# redashboard_rp2040.net
KiCad netlist of a schematic drawn in EAGLE
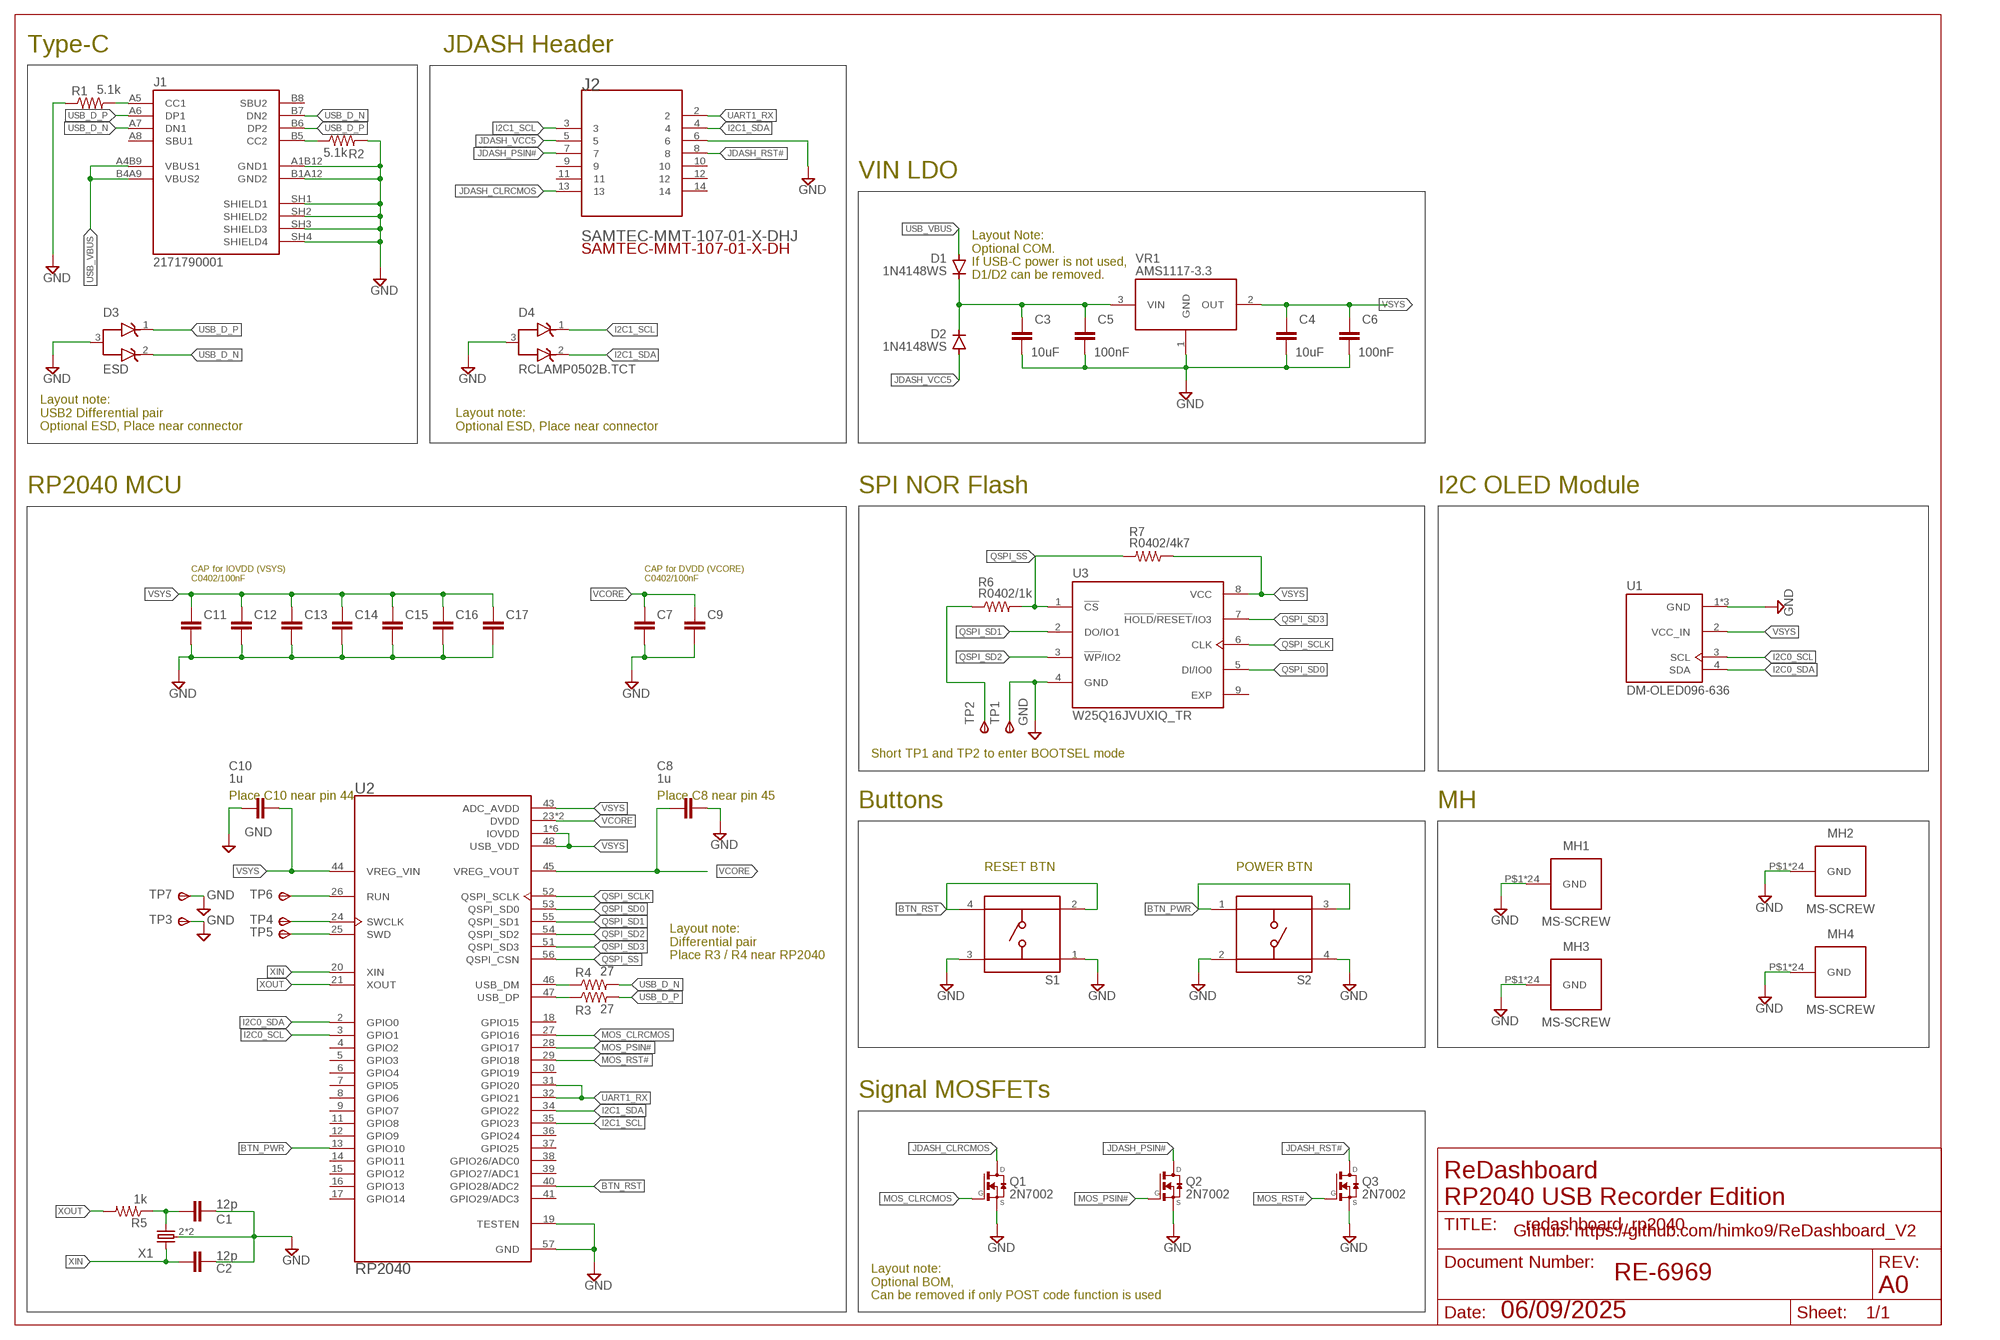
[diagram p0: schematic, sheet 1]

(export (version "E")
  (design (tool "Eeschema 10.0.6"))
  (components
    (comp (ref "C1")
      (value "12p")
      (footprint "eagle-import:CAP_0402")
      (fields
        (field (name "DIGIKEY_PART_NUMBER") "311-1014-2-ND")
        (field (name "MANUFACTURER") "Yageo")
        (field (name "MPN") "CC0402JRNPO9BN100")
        (field (name "CREATED_BY") "PCBLayout.com")
      )
      (libsource (lib "eagle-import") (part "CC0402JRNPO9BN100"))
    )
    (comp (ref "C2")
      (value "12p")
      (footprint "eagle-import:CAP_0402")
      (fields
        (field (name "DIGIKEY_PART_NUMBER") "311-1014-2-ND")
        (field (name "MANUFACTURER") "Yageo")
        (field (name "MPN") "CC0402JRNPO9BN100")
        (field (name "CREATED_BY") "PCBLayout.com")
      )
      (libsource (lib "eagle-import") (part "CC0402JRNPO9BN100"))
    )
    (comp (ref "C3")
      (value "10uF")
      (footprint "eagle-import:CAP_0603")
      (fields
        (field (name "DIGIKEY_PART_NUMBER") "311-1063-2-ND")
        (field (name "MANUFACTURER") "Yageo")
        (field (name "MPN") "CC0603JRNPO9BN270")
        (field (name "CREATED_BY") "PCBLayout.com")
      )
      (libsource (lib "eagle-import") (part "CC0603JRNPO9BN270"))
    )
    (comp (ref "C4")
      (value "10uF")
      (footprint "eagle-import:CAP_0603")
      (fields
        (field (name "DIGIKEY_PART_NUMBER") "311-1063-2-ND")
        (field (name "MANUFACTURER") "Yageo")
        (field (name "MPN") "CC0603JRNPO9BN270")
        (field (name "CREATED_BY") "PCBLayout.com")
      )
      (libsource (lib "eagle-import") (part "CC0603JRNPO9BN270"))
    )
    (comp (ref "C5")
      (value "100nF")
      (footprint "eagle-import:CAP_0402")
      (fields
        (field (name "DIGIKEY_PART_NUMBER") "311-2076-2-ND")
        (field (name "MANUFACTURER") "Yageo")
        (field (name "MPN") "CC0402CRNPO9BN1R0")
        (field (name "CREATED_BY") "PCBLayout.com")
      )
      (libsource (lib "eagle-import") (part "CC0402CRNPO9BN1R0"))
    )
    (comp (ref "C6")
      (value "100nF")
      (footprint "eagle-import:CAP_0402")
      (fields
        (field (name "DIGIKEY_PART_NUMBER") "311-2076-2-ND")
        (field (name "MANUFACTURER") "Yageo")
        (field (name "MPN") "CC0402CRNPO9BN1R0")
        (field (name "CREATED_BY") "PCBLayout.com")
      )
      (libsource (lib "eagle-import") (part "CC0402CRNPO9BN1R0"))
    )
    (comp (ref "C7")
      (value "100nF")
      (footprint "eagle-import:CAP_0402")
      (fields
        (field (name "DIGIKEY_PART_NUMBER") "311-2076-2-ND")
        (field (name "MANUFACTURER") "Yageo")
        (field (name "MPN") "CC0402CRNPO9BN1R0")
        (field (name "CREATED_BY") "PCBLayout.com")
      )
      (libsource (lib "eagle-import") (part "CC0402CRNPO9BN1R0"))
    )
    (comp (ref "C8")
      (value "1u")
      (footprint "eagle-import:CAP_0402")
      (fields
        (field (name "DIGIKEY_PART_NUMBER") "311-2076-2-ND")
        (field (name "MANUFACTURER") "Yageo")
        (field (name "MPN") "CC0402CRNPO9BN1R0")
        (field (name "CREATED_BY") "PCBLayout.com")
      )
      (libsource (lib "eagle-import") (part "CC0402CRNPO9BN1R0"))
    )
    (comp (ref "C9")
      (value "CC0402CRNPO9BN1R0")
      (footprint "eagle-import:CAP_0402")
      (fields
        (field (name "DIGIKEY_PART_NUMBER") "311-2076-2-ND")
        (field (name "MANUFACTURER") "Yageo")
        (field (name "CREATED_BY") "PCBLayout.com")
      )
      (libsource (lib "eagle-import") (part "CC0402CRNPO9BN1R0"))
    )
    (comp (ref "C10")
      (value "1u")
      (footprint "eagle-import:CAP_0402")
      (fields
        (field (name "DIGIKEY_PART_NUMBER") "311-2076-2-ND")
        (field (name "MANUFACTURER") "Yageo")
        (field (name "MPN") "CC0402CRNPO9BN1R0")
        (field (name "CREATED_BY") "PCBLayout.com")
      )
      (libsource (lib "eagle-import") (part "CC0402CRNPO9BN1R0"))
    )
    (comp (ref "C11")
      (value "100nF")
      (footprint "eagle-import:CAP_0402")
      (fields
        (field (name "DIGIKEY_PART_NUMBER") "311-2076-2-ND")
        (field (name "MANUFACTURER") "Yageo")
        (field (name "MPN") "CC0402CRNPO9BN1R0")
        (field (name "CREATED_BY") "PCBLayout.com")
      )
      (libsource (lib "eagle-import") (part "CC0402CRNPO9BN1R0"))
    )
    (comp (ref "C12")
      (value "100nF")
      (footprint "eagle-import:CAP_0402")
      (fields
        (field (name "DIGIKEY_PART_NUMBER") "311-2076-2-ND")
        (field (name "MANUFACTURER") "Yageo")
        (field (name "MPN") "CC0402CRNPO9BN1R0")
        (field (name "CREATED_BY") "PCBLayout.com")
      )
      (libsource (lib "eagle-import") (part "CC0402CRNPO9BN1R0"))
    )
    (comp (ref "C13")
      (value "100nF")
      (footprint "eagle-import:CAP_0402")
      (fields
        (field (name "DIGIKEY_PART_NUMBER") "311-2076-2-ND")
        (field (name "MANUFACTURER") "Yageo")
        (field (name "MPN") "CC0402CRNPO9BN1R0")
        (field (name "CREATED_BY") "PCBLayout.com")
      )
      (libsource (lib "eagle-import") (part "CC0402CRNPO9BN1R0"))
    )
    (comp (ref "C14")
      (value "100nF")
      (footprint "eagle-import:CAP_0402")
      (fields
        (field (name "DIGIKEY_PART_NUMBER") "311-2076-2-ND")
        (field (name "MANUFACTURER") "Yageo")
        (field (name "MPN") "CC0402CRNPO9BN1R0")
        (field (name "CREATED_BY") "PCBLayout.com")
      )
      (libsource (lib "eagle-import") (part "CC0402CRNPO9BN1R0"))
    )
    (comp (ref "C15")
      (value "100nF")
      (footprint "eagle-import:CAP_0402")
      (fields
        (field (name "DIGIKEY_PART_NUMBER") "311-2076-2-ND")
        (field (name "MANUFACTURER") "Yageo")
        (field (name "MPN") "CC0402CRNPO9BN1R0")
        (field (name "CREATED_BY") "PCBLayout.com")
      )
      (libsource (lib "eagle-import") (part "CC0402CRNPO9BN1R0"))
    )
    (comp (ref "C16")
      (value "100nF")
      (footprint "eagle-import:CAP_0402")
      (fields
        (field (name "DIGIKEY_PART_NUMBER") "311-2076-2-ND")
        (field (name "MANUFACTURER") "Yageo")
        (field (name "MPN") "CC0402CRNPO9BN1R0")
        (field (name "CREATED_BY") "PCBLayout.com")
      )
      (libsource (lib "eagle-import") (part "CC0402CRNPO9BN1R0"))
    )
    (comp (ref "C17")
      (value "100nF")
      (footprint "eagle-import:CAP_0402")
      (fields
        (field (name "DIGIKEY_PART_NUMBER") "311-2076-2-ND")
        (field (name "MANUFACTURER") "Yageo")
        (field (name "MPN") "CC0402CRNPO9BN1R0")
        (field (name "CREATED_BY") "PCBLayout.com")
      )
      (libsource (lib "eagle-import") (part "CC0402CRNPO9BN1R0"))
    )
    (comp (ref "D1")
      (value "1N4148WS")
      (footprint "eagle-import:SOD-323")
      (fields
        (field (name "DIGIKEY_PART_NUMBER") "1N4148WSFSTR-ND")
        (field (name "MANUFACTURER") "Diodes Incorporated")
        (field (name "CREATED_BY") "PCBLayout.com")
      )
      (libsource (lib "eagle-import") (part "1N4148WS"))
    )
    (comp (ref "D2")
      (value "1N4148WS")
      (footprint "eagle-import:SOD-323")
      (fields
        (field (name "DIGIKEY_PART_NUMBER") "1N4148WSFSTR-ND")
        (field (name "MANUFACTURER") "Diodes Incorporated")
        (field (name "CREATED_BY") "PCBLayout.com")
      )
      (libsource (lib "eagle-import") (part "1N4148WS"))
    )
    (comp (ref "D3")
      (value "ESD")
      (footprint "eagle-import:TVS_RCLAMP0502B.TCT")
      (fields (field (name "MF") "Semtech Corporation") (field (name "MP") "RCLAMP0502B.TCT"))
      (libsource (lib "eagle-import") (part "RCLAMP0502B.TCT"))
    )
    (comp (ref "D4")
      (value "RCLAMP0502B.TCT")
      (footprint "eagle-import:TVS_RCLAMP0502B.TCT")
      (fields (field (name "MF") "Semtech Corporation"))
      (libsource (lib "eagle-import") (part "RCLAMP0502B.TCT"))
    )
    (comp (ref "J1")
      (value "2171790001")
      (footprint "eagle-import:MOLEX_2171790001")
      (fields (field (name "MF") "Molex"))
      (libsource (lib "eagle-import") (part "2171790001"))
    )
    (comp (ref "J2")
      (value "SAMTEC-MMT-107-01-X-DHJ")
      (footprint "eagle-import:SAMTEC-MMT-107-01-X-DH")
      (fields (field (name "MF") "Samtec") (field (name "MP") "MMT-107-01-S-DH-P-TR"))
      (libsource (lib "eagle-import") (part "SAMTEC-MMT-107-01-X-DHJ"))
    )
    (comp (ref "MH1")
      (value "MS-SCREW")
      (footprint "eagle-import:MS-SCREW")
      (libsource (lib "eagle-import") (part "MS-SCREW"))
    )
    (comp (ref "MH2")
      (value "MS-SCREW")
      (footprint "eagle-import:MS-SCREW")
      (libsource (lib "eagle-import") (part "MS-SCREW"))
    )
    (comp (ref "MH3")
      (value "MS-SCREW")
      (footprint "eagle-import:MS-SCREW")
      (libsource (lib "eagle-import") (part "MS-SCREW"))
    )
    (comp (ref "MH4")
      (value "MS-SCREW")
      (footprint "eagle-import:MS-SCREW")
      (libsource (lib "eagle-import") (part "MS-SCREW"))
    )
    (comp (ref "Q1")
      (value "2N7002")
      (footprint "eagle-import:TRANSISTOR-FET_SOT23")
      (libsource (lib "eagle-import") (part "TRANSISTOR-FET_DMN2004K"))
    )
    (comp (ref "Q2")
      (value "2N7002")
      (footprint "eagle-import:TRANSISTOR-FET_SOT23")
      (libsource (lib "eagle-import") (part "TRANSISTOR-FET_DMN2004K"))
    )
    (comp (ref "Q3")
      (value "2N7002")
      (footprint "eagle-import:TRANSISTOR-FET_SOT23")
      (libsource (lib "eagle-import") (part "TRANSISTOR-FET_DMN2004K"))
    )
    (comp (ref "R1")
      (value "5.1k")
      (footprint "eagle-import:RES_0402")
      (fields
        (field (name "DIGIKEY_PART_NUMBER") "311-0.0JRTR-ND")
        (field (name "MANUFACTURER") "Yageo")
        (field (name "MPN") "RC0402JR-070RL")
        (field (name "CREATED_BY") "PCBLayout.com")
      )
      (libsource (lib "eagle-import") (part "RC0402JR-070RL"))
    )
    (comp (ref "R2")
      (value "5.1k")
      (footprint "eagle-import:RES_0402")
      (fields
        (field (name "DIGIKEY_PART_NUMBER") "311-0.0JRTR-ND")
        (field (name "MANUFACTURER") "Yageo")
        (field (name "MPN") "RC0402JR-070RL")
        (field (name "CREATED_BY") "PCBLayout.com")
      )
      (libsource (lib "eagle-import") (part "RC0402JR-070RL"))
    )
    (comp (ref "R3")
      (value "27")
      (footprint "eagle-import:RES_0402")
      (fields
        (field (name "DIGIKEY_PART_NUMBER") "311-0.0JRTR-ND")
        (field (name "MANUFACTURER") "Yageo")
        (field (name "MPN") "RC0402JR-070RL")
        (field (name "CREATED_BY") "PCBLayout.com")
      )
      (libsource (lib "eagle-import") (part "RC0402JR-070RL"))
    )
    (comp (ref "R4")
      (value "27")
      (footprint "eagle-import:RES_0402")
      (fields
        (field (name "DIGIKEY_PART_NUMBER") "311-0.0JRTR-ND")
        (field (name "MANUFACTURER") "Yageo")
        (field (name "MPN") "RC0402JR-070RL")
        (field (name "CREATED_BY") "PCBLayout.com")
      )
      (libsource (lib "eagle-import") (part "RC0402JR-070RL"))
    )
    (comp (ref "R5")
      (value "1k")
      (footprint "eagle-import:RES_0402")
      (fields
        (field (name "DIGIKEY_PART_NUMBER") "311-0.0JRTR-ND")
        (field (name "MANUFACTURER") "Yageo")
        (field (name "MPN") "RC0402JR-070RL")
        (field (name "CREATED_BY") "PCBLayout.com")
      )
      (libsource (lib "eagle-import") (part "RC0402JR-070RL"))
    )
    (comp (ref "R6")
      (value "R0402/1k")
      (footprint "eagle-import:RES_0402")
      (fields
        (field (name "DIGIKEY_PART_NUMBER") "311-0.0JRTR-ND")
        (field (name "MANUFACTURER") "Yageo")
        (field (name "MPN") "RC0402JR-070RL")
        (field (name "CREATED_BY") "PCBLayout.com")
      )
      (libsource (lib "eagle-import") (part "RC0402JR-070RL"))
    )
    (comp (ref "R7")
      (value "R0402/4k7")
      (footprint "eagle-import:RES_0402")
      (fields
        (field (name "DIGIKEY_PART_NUMBER") "311-0.0JRTR-ND")
        (field (name "MANUFACTURER") "Yageo")
        (field (name "MPN") "RC0402JR-070RL")
        (field (name "CREATED_BY") "PCBLayout.com")
      )
      (libsource (lib "eagle-import") (part "RC0402JR-070RL"))
    )
    (comp (ref "S1")
      (value "TS04-66-50-BK-260-SMT")
      (footprint "eagle-import:SW_TS04-66-50-BK-260-SMT")
      (fields (field (name "MF") "Same Sky"))
      (libsource (lib "eagle-import") (part "TS04-66-50-BK-260-SMT"))
    )
    (comp (ref "S2")
      (value "TS04-66-50-BK-260-SMT")
      (footprint "eagle-import:SW_TS04-66-50-BK-260-SMT")
      (fields (field (name "MF") "Same Sky"))
      (libsource (lib "eagle-import") (part "TS04-66-50-BK-260-SMT"))
    )
    (comp (ref "TP1")
      (value "TPSTP10SQ")
      (footprint "eagle-import:TP10SQ")
      (libsource (lib "eagle-import") (part "TPSTP10SQ"))
    )
    (comp (ref "TP2")
      (value "TPSTP10R")
      (footprint "eagle-import:TP10R")
      (libsource (lib "eagle-import") (part "TPSTP10R"))
    )
    (comp (ref "TP3")
      (value "TPSTP10SQ")
      (footprint "eagle-import:TP10SQ")
      (libsource (lib "eagle-import") (part "TPSTP10SQ"))
    )
    (comp (ref "TP4")
      (value "TPSTP10R")
      (footprint "eagle-import:TP10R")
      (libsource (lib "eagle-import") (part "TPSTP10R"))
    )
    (comp (ref "TP5")
      (value "TPSTP10R")
      (footprint "eagle-import:TP10R")
      (libsource (lib "eagle-import") (part "TPSTP10R"))
    )
    (comp (ref "TP6")
      (value "TPSTP10R")
      (footprint "eagle-import:TP10R")
      (libsource (lib "eagle-import") (part "TPSTP10R"))
    )
    (comp (ref "TP7")
      (value "TPSTP10SQ")
      (footprint "eagle-import:TP10SQ")
      (libsource (lib "eagle-import") (part "TPSTP10SQ"))
    )
    (comp (ref "U1")
      (value "DM-OLED096-636")
      (footprint "eagle-import:MODULE_DM-OLED096-636")
      (fields (field (name "MF") "Display Module"))
      (libsource (lib "eagle-import") (part "DM-OLED096-636"))
    )
    (comp (ref "U2")
      (value "RP2040")
      (footprint "eagle-import:QFN40P700X700X90-57N")
      (fields (field (name "MF") "Raspberry Pi"))
      (libsource (lib "eagle-import") (part "RP2040"))
    )
    (comp (ref "U3")
      (value "W25Q16JVUXIQ_TR")
      (footprint "eagle-import:IC_W25Q16JVUXIQ_TR")
      (fields (field (name "MF") "Winbond") (field (name "MP") "W25Q16JVUXIQ TR"))
      (libsource (lib "eagle-import") (part "W25Q16JVUXIQ_TR"))
    )
    (comp (ref "VR1")
      (value "AMS1117-3.3")
      (footprint "eagle-import:VREG_AZ1117CR2-5.0TRG1")
      (fields (field (name "MF") "Diodes Zetex") (field (name "MP") "AZ1117CR2-5.0TRG1"))
      (libsource (lib "eagle-import") (part "AZ1117CR2-5.0TRG1"))
    )
    (comp (ref "X1")
      (value "KX-6")
      (footprint "eagle-import:2.5X2.0_KX-6")
      (libsource (lib "eagle-import") (part "KX-6"))
    )
  )
  (nets
    (net (code "1") (name "BTN_PWR") (class "Default")
      (node (ref "S2") (pin "1") (pinfunction "1_1") (pintype "passive"))
      (node (ref "S2") (pin "3") (pinfunction "3_3") (pintype "passive"))
      (node (ref "U2") (pin "13") (pinfunction "GPIO10_13") (pintype "bidirectional"))
    )
    (net (code "2") (name "BTN_RST") (class "Default")
      (node (ref "S1") (pin "2") (pinfunction "2_2") (pintype "passive"))
      (node (ref "S1") (pin "4") (pinfunction "4_4") (pintype "passive"))
      (node (ref "U2") (pin "40") (pinfunction "GPIO28/ADC2_40") (pintype "bidirectional"))
    )
    (net (code "3") (name "GND") (class "Default")
      (node (ref "C1") (pin "2") (pinfunction "2_2") (pintype "passive"))
      (node (ref "C10") (pin "1") (pinfunction "1_1") (pintype "passive"))
      (node (ref "C11") (pin "2") (pinfunction "2_2") (pintype "passive"))
      (node (ref "C12") (pin "2") (pinfunction "2_2") (pintype "passive"))
      (node (ref "C13") (pin "2") (pinfunction "2_2") (pintype "passive"))
      (node (ref "C14") (pin "2") (pinfunction "2_2") (pintype "passive"))
      (node (ref "C15") (pin "2") (pinfunction "2_2") (pintype "passive"))
      (node (ref "C16") (pin "2") (pinfunction "2_2") (pintype "passive"))
      (node (ref "C17") (pin "2") (pinfunction "2_2") (pintype "passive"))
      (node (ref "C2") (pin "2") (pinfunction "2_2") (pintype "passive"))
      (node (ref "C3") (pin "2") (pinfunction "2_2") (pintype "passive"))
      (node (ref "C4") (pin "2") (pinfunction "2_2") (pintype "passive"))
      (node (ref "C5") (pin "2") (pinfunction "2_2") (pintype "passive"))
      (node (ref "C6") (pin "2") (pinfunction "2_2") (pintype "passive"))
      (node (ref "C7") (pin "2") (pinfunction "2_2") (pintype "passive"))
      (node (ref "C8") (pin "2") (pinfunction "2_2") (pintype "passive"))
      (node (ref "C9") (pin "2") (pinfunction "2_2") (pintype "passive"))
      (node (ref "D3") (pin "3") (pinfunction "A_3") (pintype "passive"))
      (node (ref "D4") (pin "3") (pinfunction "A_3") (pintype "passive"))
      (node (ref "J1") (pin "A1B12") (pinfunction "GND1_A1B12") (pintype "power_in"))
      (node (ref "J1") (pin "B1A12") (pinfunction "GND2_B1A12") (pintype "power_in"))
      (node (ref "J1") (pin "SH1") (pinfunction "SHIELD1_SH1") (pintype "passive"))
      (node (ref "J1") (pin "SH2") (pinfunction "SHIELD2_SH2") (pintype "passive"))
      (node (ref "J1") (pin "SH3") (pinfunction "SHIELD3_SH3") (pintype "passive"))
      (node (ref "J1") (pin "SH4") (pinfunction "SHIELD4_SH4") (pintype "passive"))
      (node (ref "J2") (pin "6") (pinfunction "6_6") (pintype "passive"))
      (node (ref "MH1") (pin "P$1") (pinfunction "GND_P$1") (pintype "bidirectional"))
      (node (ref "MH1") (pin "P$10") (pinfunction "GND_P$10") (pintype "bidirectional"))
      (node (ref "MH1") (pin "P$11") (pinfunction "GND_P$11") (pintype "bidirectional"))
      (node (ref "MH1") (pin "P$12") (pinfunction "GND_P$12") (pintype "bidirectional"))
      (node (ref "MH1") (pin "P$13") (pinfunction "GND_P$13") (pintype "bidirectional"))
      (node (ref "MH1") (pin "P$14") (pinfunction "GND_P$14") (pintype "bidirectional"))
      (node (ref "MH1") (pin "P$15") (pinfunction "GND_P$15") (pintype "bidirectional"))
      (node (ref "MH1") (pin "P$16") (pinfunction "GND_P$16") (pintype "bidirectional"))
      (node (ref "MH1") (pin "P$17") (pinfunction "GND_P$17") (pintype "bidirectional"))
      (node (ref "MH1") (pin "P$18") (pinfunction "GND_P$18") (pintype "bidirectional"))
      (node (ref "MH1") (pin "P$19") (pinfunction "GND_P$19") (pintype "bidirectional"))
      (node (ref "MH1") (pin "P$2") (pinfunction "GND_P$2") (pintype "bidirectional"))
      (node (ref "MH1") (pin "P$20") (pinfunction "GND_P$20") (pintype "bidirectional"))
      (node (ref "MH1") (pin "P$21") (pinfunction "GND_P$21") (pintype "bidirectional"))
      (node (ref "MH1") (pin "P$22") (pinfunction "GND_P$22") (pintype "bidirectional"))
      (node (ref "MH1") (pin "P$23") (pinfunction "GND_P$23") (pintype "bidirectional"))
      (node (ref "MH1") (pin "P$24") (pinfunction "GND_P$24") (pintype "bidirectional"))
      (node (ref "MH1") (pin "P$3") (pinfunction "GND_P$3") (pintype "bidirectional"))
      (node (ref "MH1") (pin "P$4") (pinfunction "GND_P$4") (pintype "bidirectional"))
      (node (ref "MH1") (pin "P$5") (pinfunction "GND_P$5") (pintype "bidirectional"))
      (node (ref "MH1") (pin "P$6") (pinfunction "GND_P$6") (pintype "bidirectional"))
      (node (ref "MH1") (pin "P$7") (pinfunction "GND_P$7") (pintype "bidirectional"))
      (node (ref "MH1") (pin "P$8") (pinfunction "GND_P$8") (pintype "bidirectional"))
      (node (ref "MH1") (pin "P$9") (pinfunction "GND_P$9") (pintype "bidirectional"))
      (node (ref "MH2") (pin "P$1") (pinfunction "GND_P$1") (pintype "bidirectional"))
      (node (ref "MH2") (pin "P$10") (pinfunction "GND_P$10") (pintype "bidirectional"))
      (node (ref "MH2") (pin "P$11") (pinfunction "GND_P$11") (pintype "bidirectional"))
      (node (ref "MH2") (pin "P$12") (pinfunction "GND_P$12") (pintype "bidirectional"))
      (node (ref "MH2") (pin "P$13") (pinfunction "GND_P$13") (pintype "bidirectional"))
      (node (ref "MH2") (pin "P$14") (pinfunction "GND_P$14") (pintype "bidirectional"))
      (node (ref "MH2") (pin "P$15") (pinfunction "GND_P$15") (pintype "bidirectional"))
      (node (ref "MH2") (pin "P$16") (pinfunction "GND_P$16") (pintype "bidirectional"))
      (node (ref "MH2") (pin "P$17") (pinfunction "GND_P$17") (pintype "bidirectional"))
      (node (ref "MH2") (pin "P$18") (pinfunction "GND_P$18") (pintype "bidirectional"))
      (node (ref "MH2") (pin "P$19") (pinfunction "GND_P$19") (pintype "bidirectional"))
      (node (ref "MH2") (pin "P$2") (pinfunction "GND_P$2") (pintype "bidirectional"))
      (node (ref "MH2") (pin "P$20") (pinfunction "GND_P$20") (pintype "bidirectional"))
      (node (ref "MH2") (pin "P$21") (pinfunction "GND_P$21") (pintype "bidirectional"))
      (node (ref "MH2") (pin "P$22") (pinfunction "GND_P$22") (pintype "bidirectional"))
      (node (ref "MH2") (pin "P$23") (pinfunction "GND_P$23") (pintype "bidirectional"))
      (node (ref "MH2") (pin "P$24") (pinfunction "GND_P$24") (pintype "bidirectional"))
      (node (ref "MH2") (pin "P$3") (pinfunction "GND_P$3") (pintype "bidirectional"))
      (node (ref "MH2") (pin "P$4") (pinfunction "GND_P$4") (pintype "bidirectional"))
      (node (ref "MH2") (pin "P$5") (pinfunction "GND_P$5") (pintype "bidirectional"))
      (node (ref "MH2") (pin "P$6") (pinfunction "GND_P$6") (pintype "bidirectional"))
      (node (ref "MH2") (pin "P$7") (pinfunction "GND_P$7") (pintype "bidirectional"))
      (node (ref "MH2") (pin "P$8") (pinfunction "GND_P$8") (pintype "bidirectional"))
      (node (ref "MH2") (pin "P$9") (pinfunction "GND_P$9") (pintype "bidirectional"))
      (node (ref "MH3") (pin "P$1") (pinfunction "GND_P$1") (pintype "bidirectional"))
      (node (ref "MH3") (pin "P$10") (pinfunction "GND_P$10") (pintype "bidirectional"))
      (node (ref "MH3") (pin "P$11") (pinfunction "GND_P$11") (pintype "bidirectional"))
      (node (ref "MH3") (pin "P$12") (pinfunction "GND_P$12") (pintype "bidirectional"))
      (node (ref "MH3") (pin "P$13") (pinfunction "GND_P$13") (pintype "bidirectional"))
      (node (ref "MH3") (pin "P$14") (pinfunction "GND_P$14") (pintype "bidirectional"))
      (node (ref "MH3") (pin "P$15") (pinfunction "GND_P$15") (pintype "bidirectional"))
      (node (ref "MH3") (pin "P$16") (pinfunction "GND_P$16") (pintype "bidirectional"))
      (node (ref "MH3") (pin "P$17") (pinfunction "GND_P$17") (pintype "bidirectional"))
      (node (ref "MH3") (pin "P$18") (pinfunction "GND_P$18") (pintype "bidirectional"))
      (node (ref "MH3") (pin "P$19") (pinfunction "GND_P$19") (pintype "bidirectional"))
      (node (ref "MH3") (pin "P$2") (pinfunction "GND_P$2") (pintype "bidirectional"))
      (node (ref "MH3") (pin "P$20") (pinfunction "GND_P$20") (pintype "bidirectional"))
      (node (ref "MH3") (pin "P$21") (pinfunction "GND_P$21") (pintype "bidirectional"))
      (node (ref "MH3") (pin "P$22") (pinfunction "GND_P$22") (pintype "bidirectional"))
      (node (ref "MH3") (pin "P$23") (pinfunction "GND_P$23") (pintype "bidirectional"))
      (node (ref "MH3") (pin "P$24") (pinfunction "GND_P$24") (pintype "bidirectional"))
      (node (ref "MH3") (pin "P$3") (pinfunction "GND_P$3") (pintype "bidirectional"))
      (node (ref "MH3") (pin "P$4") (pinfunction "GND_P$4") (pintype "bidirectional"))
      (node (ref "MH3") (pin "P$5") (pinfunction "GND_P$5") (pintype "bidirectional"))
      (node (ref "MH3") (pin "P$6") (pinfunction "GND_P$6") (pintype "bidirectional"))
      (node (ref "MH3") (pin "P$7") (pinfunction "GND_P$7") (pintype "bidirectional"))
      (node (ref "MH3") (pin "P$8") (pinfunction "GND_P$8") (pintype "bidirectional"))
      (node (ref "MH3") (pin "P$9") (pinfunction "GND_P$9") (pintype "bidirectional"))
      (node (ref "MH4") (pin "P$1") (pinfunction "GND_P$1") (pintype "bidirectional"))
      (node (ref "MH4") (pin "P$10") (pinfunction "GND_P$10") (pintype "bidirectional"))
      (node (ref "MH4") (pin "P$11") (pinfunction "GND_P$11") (pintype "bidirectional"))
      (node (ref "MH4") (pin "P$12") (pinfunction "GND_P$12") (pintype "bidirectional"))
      (node (ref "MH4") (pin "P$13") (pinfunction "GND_P$13") (pintype "bidirectional"))
      (node (ref "MH4") (pin "P$14") (pinfunction "GND_P$14") (pintype "bidirectional"))
      (node (ref "MH4") (pin "P$15") (pinfunction "GND_P$15") (pintype "bidirectional"))
      (node (ref "MH4") (pin "P$16") (pinfunction "GND_P$16") (pintype "bidirectional"))
      (node (ref "MH4") (pin "P$17") (pinfunction "GND_P$17") (pintype "bidirectional"))
      (node (ref "MH4") (pin "P$18") (pinfunction "GND_P$18") (pintype "bidirectional"))
      (node (ref "MH4") (pin "P$19") (pinfunction "GND_P$19") (pintype "bidirectional"))
      (node (ref "MH4") (pin "P$2") (pinfunction "GND_P$2") (pintype "bidirectional"))
      (node (ref "MH4") (pin "P$20") (pinfunction "GND_P$20") (pintype "bidirectional"))
      (node (ref "MH4") (pin "P$21") (pinfunction "GND_P$21") (pintype "bidirectional"))
      (node (ref "MH4") (pin "P$22") (pinfunction "GND_P$22") (pintype "bidirectional"))
      (node (ref "MH4") (pin "P$23") (pinfunction "GND_P$23") (pintype "bidirectional"))
      (node (ref "MH4") (pin "P$24") (pinfunction "GND_P$24") (pintype "bidirectional"))
      (node (ref "MH4") (pin "P$3") (pinfunction "GND_P$3") (pintype "bidirectional"))
      (node (ref "MH4") (pin "P$4") (pinfunction "GND_P$4") (pintype "bidirectional"))
      (node (ref "MH4") (pin "P$5") (pinfunction "GND_P$5") (pintype "bidirectional"))
      (node (ref "MH4") (pin "P$6") (pinfunction "GND_P$6") (pintype "bidirectional"))
      (node (ref "MH4") (pin "P$7") (pinfunction "GND_P$7") (pintype "bidirectional"))
      (node (ref "MH4") (pin "P$8") (pinfunction "GND_P$8") (pintype "bidirectional"))
      (node (ref "MH4") (pin "P$9") (pinfunction "GND_P$9") (pintype "bidirectional"))
      (node (ref "Q1") (pin "2") (pinfunction "S_2") (pintype "passive"))
      (node (ref "Q2") (pin "2") (pinfunction "S_2") (pintype "passive"))
      (node (ref "Q3") (pin "2") (pinfunction "S_2") (pintype "passive"))
      (node (ref "R1") (pin "1") (pinfunction "1_1") (pintype "passive"))
      (node (ref "R2") (pin "2") (pinfunction "2_2") (pintype "passive"))
      (node (ref "S1") (pin "1") (pinfunction "1_1") (pintype "passive"))
      (node (ref "S1") (pin "3") (pinfunction "3_3") (pintype "passive"))
      (node (ref "S2") (pin "2") (pinfunction "2_2") (pintype "passive"))
      (node (ref "S2") (pin "4") (pinfunction "4_4") (pintype "passive"))
      (node (ref "TP1") (pin "TP") (pinfunction "PP_TP") (pintype "input"))
      (node (ref "TP3") (pin "TP") (pinfunction "PP_TP") (pintype "input"))
      (node (ref "TP7") (pin "TP") (pinfunction "PP_TP") (pintype "input"))
      (node (ref "U1") (pin "1") (pinfunction "GND_1") (pintype "power_in"))
      (node (ref "U1") (pin "S3") (pinfunction "GND_S3") (pintype "power_in"))
      (node (ref "U1") (pin "S4") (pinfunction "GND_S4") (pintype "power_in"))
      (node (ref "U2") (pin "19") (pinfunction "TESTEN_19") (pintype "passive"))
      (node (ref "U2") (pin "57") (pinfunction "GND_57") (pintype "power_in"))
      (node (ref "U3") (pin "4") (pinfunction "GND_4") (pintype "power_in"))
      (node (ref "VR1") (pin "1") (pinfunction "GND_1") (pintype "power_in"))
      (node (ref "X1") (pin "2") (pinfunction "3_2") (pintype "passive"))
      (node (ref "X1") (pin "4") (pinfunction "3_4") (pintype "passive"))
    )
    (net (code "4") (name "I2C0_SCL") (class "Default")
      (node (ref "U1") (pin "3") (pinfunction "SCL_3") (pintype "input"))
      (node (ref "U2") (pin "3") (pinfunction "GPIO1_3") (pintype "bidirectional"))
    )
    (net (code "5") (name "I2C0_SDA") (class "Default")
      (node (ref "U1") (pin "4") (pinfunction "SDA_4") (pintype "bidirectional"))
      (node (ref "U2") (pin "2") (pinfunction "GPIO0_2") (pintype "bidirectional"))
    )
    (net (code "6") (name "I2C1_SCL") (class "Default")
      (node (ref "D4") (pin "1") (pinfunction "K1_1") (pintype "passive"))
      (node (ref "J2") (pin "3") (pinfunction "3_3") (pintype "passive"))
      (node (ref "U2") (pin "35") (pinfunction "GPIO23_35") (pintype "bidirectional"))
    )
    (net (code "7") (name "I2C1_SDA") (class "Default")
      (node (ref "D4") (pin "2") (pinfunction "K2_2") (pintype "passive"))
      (node (ref "J2") (pin "4") (pinfunction "4_4") (pintype "passive"))
      (node (ref "U2") (pin "34") (pinfunction "GPIO22_34") (pintype "bidirectional"))
    )
    (net (code "8") (name "JDASH_CLRCMOS") (class "Default")
      (node (ref "J2") (pin "13") (pinfunction "13_13") (pintype "passive"))
      (node (ref "Q1") (pin "3") (pinfunction "D_3") (pintype "passive"))
    )
    (net (code "9") (name "JDASH_PSIN#") (class "Default")
      (node (ref "J2") (pin "7") (pinfunction "7_7") (pintype "passive"))
      (node (ref "Q2") (pin "3") (pinfunction "D_3") (pintype "passive"))
    )
    (net (code "10") (name "JDASH_RST#") (class "Default")
      (node (ref "J2") (pin "8") (pinfunction "8_8") (pintype "passive"))
      (node (ref "Q3") (pin "3") (pinfunction "D_3") (pintype "passive"))
    )
    (net (code "11") (name "JDASH_VCC5") (class "Default")
      (node (ref "D2") (pin "A") (pinfunction "A_A") (pintype "passive"))
      (node (ref "J2") (pin "5") (pinfunction "5_5") (pintype "passive"))
    )
    (net (code "12") (name "MOS_CLRCMOS") (class "Default")
      (node (ref "Q1") (pin "1") (pinfunction "G_1") (pintype "passive"))
      (node (ref "U2") (pin "27") (pinfunction "GPIO16_27") (pintype "bidirectional"))
    )
    (net (code "13") (name "MOS_PSIN#") (class "Default")
      (node (ref "Q2") (pin "1") (pinfunction "G_1") (pintype "passive"))
      (node (ref "U2") (pin "28") (pinfunction "GPIO17_28") (pintype "bidirectional"))
    )
    (net (code "14") (name "MOS_RST#") (class "Default")
      (node (ref "Q3") (pin "1") (pinfunction "G_1") (pintype "passive"))
      (node (ref "U2") (pin "29") (pinfunction "GPIO18_29") (pintype "bidirectional"))
    )
    (net (code "15") (name "Net-(J1-CC1)") (class "Default")
      (node (ref "J1") (pin "A5") (pinfunction "CC1_A5") (pintype "bidirectional"))
      (node (ref "R1") (pin "2") (pinfunction "2_2") (pintype "passive"))
    )
    (net (code "16") (name "Net-(J1-CC2)") (class "Default")
      (node (ref "J1") (pin "B5") (pinfunction "CC2_B5") (pintype "bidirectional"))
      (node (ref "R2") (pin "1") (pinfunction "1_1") (pintype "passive"))
    )
    (net (code "17") (name "Net-(TP2-PP)") (class "Default")
      (node (ref "R6") (pin "1") (pinfunction "1_1") (pintype "passive"))
      (node (ref "TP2") (pin "TP") (pinfunction "PP_TP") (pintype "input"))
    )
    (net (code "18") (name "Net-(TP4-PP)") (class "Default")
      (node (ref "TP4") (pin "TP") (pinfunction "PP_TP") (pintype "input"))
      (node (ref "U2") (pin "24") (pinfunction "SWCLK_24") (pintype "input"))
    )
    (net (code "19") (name "Net-(TP5-PP)") (class "Default")
      (node (ref "TP5") (pin "TP") (pinfunction "PP_TP") (pintype "input"))
      (node (ref "U2") (pin "25") (pinfunction "SWD_25") (pintype "bidirectional"))
    )
    (net (code "20") (name "Net-(TP6-PP)") (class "Default")
      (node (ref "TP6") (pin "TP") (pinfunction "PP_TP") (pintype "input"))
      (node (ref "U2") (pin "26") (pinfunction "RUN_26") (pintype "input"))
    )
    (net (code "21") (name "Net-(U2-USB_DM)") (class "Default")
      (node (ref "R4") (pin "1") (pinfunction "1_1") (pintype "passive"))
      (node (ref "U2") (pin "46") (pinfunction "USB_DM_46") (pintype "bidirectional"))
    )
    (net (code "22") (name "Net-(U2-USB_DP)") (class "Default")
      (node (ref "R3") (pin "1") (pinfunction "1_1") (pintype "passive"))
      (node (ref "U2") (pin "47") (pinfunction "USB_DP_47") (pintype "bidirectional"))
    )
    (net (code "23") (name "Net-(VR1-VIN)") (class "Default")
      (node (ref "C3") (pin "1") (pinfunction "1_1") (pintype "passive"))
      (node (ref "C5") (pin "1") (pinfunction "1_1") (pintype "passive"))
      (node (ref "D1") (pin "C") (pinfunction "C_C") (pintype "passive"))
      (node (ref "D2") (pin "C") (pinfunction "C_C") (pintype "passive"))
      (node (ref "VR1") (pin "3") (pinfunction "VIN_3") (pintype "power_in"))
    )
    (net (code "24") (name "Net-(X1-2)") (class "Default")
      (node (ref "C1") (pin "1") (pinfunction "1_1") (pintype "passive"))
      (node (ref "R5") (pin "1") (pinfunction "1_1") (pintype "passive"))
      (node (ref "X1") (pin "3") (pinfunction "2_3") (pintype "passive"))
    )
    (net (code "25") (name "QSPI_SCLK") (class "Default")
      (node (ref "U2") (pin "52") (pinfunction "QSPI_SCLK_52") (pintype "bidirectional"))
      (node (ref "U3") (pin "6") (pinfunction "CLK_6") (pintype "input"))
    )
    (net (code "26") (name "QSPI_SD0") (class "Default")
      (node (ref "U2") (pin "53") (pinfunction "QSPI_SD0_53") (pintype "bidirectional"))
      (node (ref "U3") (pin "5") (pinfunction "DI/IO0_5") (pintype "bidirectional"))
    )
    (net (code "27") (name "QSPI_SD1") (class "Default")
      (node (ref "U2") (pin "55") (pinfunction "QSPI_SD1_55") (pintype "bidirectional"))
      (node (ref "U3") (pin "2") (pinfunction "DO/IO1_2") (pintype "bidirectional"))
    )
    (net (code "28") (name "QSPI_SD2") (class "Default")
      (node (ref "U2") (pin "54") (pinfunction "QSPI_SD2_54") (pintype "bidirectional"))
      (node (ref "U3") (pin "3") (pinfunction "~{WP}/IO2_3") (pintype "bidirectional"))
    )
    (net (code "29") (name "QSPI_SD3") (class "Default")
      (node (ref "U2") (pin "51") (pinfunction "QSPI_SD3_51") (pintype "bidirectional"))
      (node (ref "U3") (pin "7") (pinfunction "~{HOLD}/~{RESET}/IO3_7") (pintype "bidirectional"))
    )
    (net (code "30") (name "QSPI_SS") (class "Default")
      (node (ref "R6") (pin "2") (pinfunction "2_2") (pintype "passive"))
      (node (ref "R7") (pin "2") (pinfunction "2_2") (pintype "passive"))
      (node (ref "U2") (pin "56") (pinfunction "QSPI_CSN_56") (pintype "bidirectional"))
      (node (ref "U3") (pin "1") (pinfunction "~{CS}_1") (pintype "input"))
    )
    (net (code "31") (name "UART1_RX") (class "Default")
      (node (ref "J2") (pin "2") (pinfunction "2_2") (pintype "passive"))
      (node (ref "U2") (pin "31") (pinfunction "GPIO20_31") (pintype "bidirectional"))
      (node (ref "U2") (pin "32") (pinfunction "GPIO21_32") (pintype "bidirectional"))
    )
    (net (code "32") (name "USB_D_N") (class "Default")
      (node (ref "D3") (pin "2") (pinfunction "K2_2") (pintype "passive"))
      (node (ref "J1") (pin "A7") (pinfunction "DN1_A7") (pintype "bidirectional"))
      (node (ref "J1") (pin "B7") (pinfunction "DN2_B7") (pintype "bidirectional"))
      (node (ref "R4") (pin "2") (pinfunction "2_2") (pintype "passive"))
    )
    (net (code "33") (name "USB_D_P") (class "Default")
      (node (ref "D3") (pin "1") (pinfunction "K1_1") (pintype "passive"))
      (node (ref "J1") (pin "A6") (pinfunction "DP1_A6") (pintype "bidirectional"))
      (node (ref "J1") (pin "B6") (pinfunction "DP2_B6") (pintype "bidirectional"))
      (node (ref "R3") (pin "2") (pinfunction "2_2") (pintype "passive"))
    )
    (net (code "34") (name "USB_VBUS") (class "Default")
      (node (ref "D1") (pin "A") (pinfunction "A_A") (pintype "passive"))
      (node (ref "J1") (pin "A4B9") (pinfunction "VBUS1_A4B9") (pintype "power_in"))
      (node (ref "J1") (pin "B4A9") (pinfunction "VBUS2_B4A9") (pintype "power_in"))
    )
    (net (code "35") (name "VCORE") (class "Default")
      (node (ref "C7") (pin "1") (pinfunction "1_1") (pintype "passive"))
      (node (ref "C8") (pin "1") (pinfunction "1_1") (pintype "passive"))
      (node (ref "C9") (pin "1") (pinfunction "1_1") (pintype "passive"))
      (node (ref "U2") (pin "23") (pinfunction "DVDD_23") (pintype "power_in"))
      (node (ref "U2") (pin "45") (pinfunction "VREG_VOUT_45") (pintype "output"))
      (node (ref "U2") (pin "50") (pinfunction "DVDD_50") (pintype "power_in"))
    )
    (net (code "36") (name "VSYS") (class "Default")
      (node (ref "C10") (pin "2") (pinfunction "2_2") (pintype "passive"))
      (node (ref "C11") (pin "1") (pinfunction "1_1") (pintype "passive"))
      (node (ref "C12") (pin "1") (pinfunction "1_1") (pintype "passive"))
      (node (ref "C13") (pin "1") (pinfunction "1_1") (pintype "passive"))
      (node (ref "C14") (pin "1") (pinfunction "1_1") (pintype "passive"))
      (node (ref "C15") (pin "1") (pinfunction "1_1") (pintype "passive"))
      (node (ref "C16") (pin "1") (pinfunction "1_1") (pintype "passive"))
      (node (ref "C17") (pin "1") (pinfunction "1_1") (pintype "passive"))
      (node (ref "C4") (pin "1") (pinfunction "1_1") (pintype "passive"))
      (node (ref "C6") (pin "1") (pinfunction "1_1") (pintype "passive"))
      (node (ref "R7") (pin "1") (pinfunction "1_1") (pintype "passive"))
      (node (ref "U1") (pin "2") (pinfunction "VCC_IN_2") (pintype "power_in"))
      (node (ref "U2") (pin "1") (pinfunction "IOVDD_1") (pintype "power_in"))
      (node (ref "U2") (pin "10") (pinfunction "IOVDD_10") (pintype "power_in"))
      (node (ref "U2") (pin "22") (pinfunction "IOVDD_22") (pintype "power_in"))
      (node (ref "U2") (pin "33") (pinfunction "IOVDD_33") (pintype "power_in"))
      (node (ref "U2") (pin "42") (pinfunction "IOVDD_42") (pintype "power_in"))
      (node (ref "U2") (pin "43") (pinfunction "ADC_AVDD_43") (pintype "power_in"))
      (node (ref "U2") (pin "44") (pinfunction "VREG_VIN_44") (pintype "input"))
      (node (ref "U2") (pin "48") (pinfunction "USB_VDD_48") (pintype "power_in"))
      (node (ref "U2") (pin "49") (pinfunction "IOVDD_49") (pintype "power_in"))
      (node (ref "U3") (pin "8") (pinfunction "VCC_8") (pintype "power_in"))
      (node (ref "VR1") (pin "2") (pinfunction "OUT_2") (pintype "output"))
    )
    (net (code "37") (name "XIN") (class "Default")
      (node (ref "C2") (pin "1") (pinfunction "1_1") (pintype "passive"))
      (node (ref "U2") (pin "20") (pinfunction "XIN_20") (pintype "input"))
      (node (ref "X1") (pin "1") (pinfunction "1_1") (pintype "passive"))
    )
    (net (code "38") (name "XOUT") (class "Default")
      (node (ref "R5") (pin "2") (pinfunction "2_2") (pintype "passive"))
      (node (ref "U2") (pin "21") (pinfunction "XOUT_21") (pintype "output"))
    )
    (net (code "39") (name "unconnected-(J1-SBU1-PadA8)") (class "Default")
      (node (ref "J1") (pin "A8") (pinfunction "SBU1_A8") (pintype "bidirectional"))
    )
    (net (code "40") (name "unconnected-(J1-SBU2-PadB8)") (class "Default")
      (node (ref "J1") (pin "B8") (pinfunction "SBU2_B8") (pintype "bidirectional"))
    )
    (net (code "41") (name "unconnected-(J2-Pad9)") (class "Default")
      (node (ref "J2") (pin "9") (pinfunction "9_9") (pintype "passive"))
    )
    (net (code "42") (name "unconnected-(J2-Pad10)") (class "Default")
      (node (ref "J2") (pin "10") (pinfunction "10_10") (pintype "passive"))
    )
    (net (code "43") (name "unconnected-(J2-Pad11)") (class "Default")
      (node (ref "J2") (pin "11") (pinfunction "11_11") (pintype "passive"))
    )
    (net (code "44") (name "unconnected-(J2-Pad12)") (class "Default")
      (node (ref "J2") (pin "12") (pinfunction "12_12") (pintype "passive"))
    )
    (net (code "45") (name "unconnected-(J2-Pad14)") (class "Default")
      (node (ref "J2") (pin "14") (pinfunction "14_14") (pintype "passive"))
    )
    (net (code "46") (name "unconnected-(U2-GPIO2-Pad4)") (class "Default")
      (node (ref "U2") (pin "4") (pinfunction "GPIO2_4") (pintype "bidirectional"))
    )
    (net (code "47") (name "unconnected-(U2-GPIO3-Pad5)") (class "Default")
      (node (ref "U2") (pin "5") (pinfunction "GPIO3_5") (pintype "bidirectional"))
    )
    (net (code "48") (name "unconnected-(U2-GPIO4-Pad6)") (class "Default")
      (node (ref "U2") (pin "6") (pinfunction "GPIO4_6") (pintype "bidirectional"))
    )
    (net (code "49") (name "unconnected-(U2-GPIO5-Pad7)") (class "Default")
      (node (ref "U2") (pin "7") (pinfunction "GPIO5_7") (pintype "bidirectional"))
    )
    (net (code "50") (name "unconnected-(U2-GPIO6-Pad8)") (class "Default")
      (node (ref "U2") (pin "8") (pinfunction "GPIO6_8") (pintype "bidirectional"))
    )
    (net (code "51") (name "unconnected-(U2-GPIO7-Pad9)") (class "Default")
      (node (ref "U2") (pin "9") (pinfunction "GPIO7_9") (pintype "bidirectional"))
    )
    (net (code "52") (name "unconnected-(U2-GPIO8-Pad11)") (class "Default")
      (node (ref "U2") (pin "11") (pinfunction "GPIO8_11") (pintype "bidirectional"))
    )
    (net (code "53") (name "unconnected-(U2-GPIO9-Pad12)") (class "Default")
      (node (ref "U2") (pin "12") (pinfunction "GPIO9_12") (pintype "bidirectional"))
    )
    (net (code "54") (name "unconnected-(U2-GPIO11-Pad14)") (class "Default")
      (node (ref "U2") (pin "14") (pinfunction "GPIO11_14") (pintype "bidirectional"))
    )
    (net (code "55") (name "unconnected-(U2-GPIO12-Pad15)") (class "Default")
      (node (ref "U2") (pin "15") (pinfunction "GPIO12_15") (pintype "bidirectional"))
    )
    (net (code "56") (name "unconnected-(U2-GPIO13-Pad16)") (class "Default")
      (node (ref "U2") (pin "16") (pinfunction "GPIO13_16") (pintype "bidirectional"))
    )
    (net (code "57") (name "unconnected-(U2-GPIO14-Pad17)") (class "Default")
      (node (ref "U2") (pin "17") (pinfunction "GPIO14_17") (pintype "bidirectional"))
    )
    (net (code "58") (name "unconnected-(U2-GPIO15-Pad18)") (class "Default")
      (node (ref "U2") (pin "18") (pinfunction "GPIO15_18") (pintype "bidirectional"))
    )
    (net (code "59") (name "unconnected-(U2-GPIO19-Pad30)") (class "Default")
      (node (ref "U2") (pin "30") (pinfunction "GPIO19_30") (pintype "bidirectional"))
    )
    (net (code "60") (name "unconnected-(U2-GPIO24-Pad36)") (class "Default")
      (node (ref "U2") (pin "36") (pinfunction "GPIO24_36") (pintype "bidirectional"))
    )
    (net (code "61") (name "unconnected-(U2-GPIO25-Pad37)") (class "Default")
      (node (ref "U2") (pin "37") (pinfunction "GPIO25_37") (pintype "bidirectional"))
    )
    (net (code "62") (name "unconnected-(U2-GPIO26{slash}ADC0-Pad38)") (class "Default")
      (node (ref "U2") (pin "38") (pinfunction "GPIO26/ADC0_38") (pintype "bidirectional"))
    )
    (net (code "63") (name "unconnected-(U2-GPIO27{slash}ADC1-Pad39)") (class "Default")
      (node (ref "U2") (pin "39") (pinfunction "GPIO27/ADC1_39") (pintype "bidirectional"))
    )
    (net (code "64") (name "unconnected-(U2-GPIO29{slash}ADC3-Pad41)") (class "Default")
      (node (ref "U2") (pin "41") (pinfunction "GPIO29/ADC3_41") (pintype "bidirectional"))
    )
    (net (code "65") (name "unconnected-(U3-EXP-Pad9)") (class "Default")
      (node (ref "U3") (pin "9") (pinfunction "EXP_9") (pintype "passive"))
    )
  )
)
